# wifistation.net
KiCad netlist of a schematic drawn in EAGLE
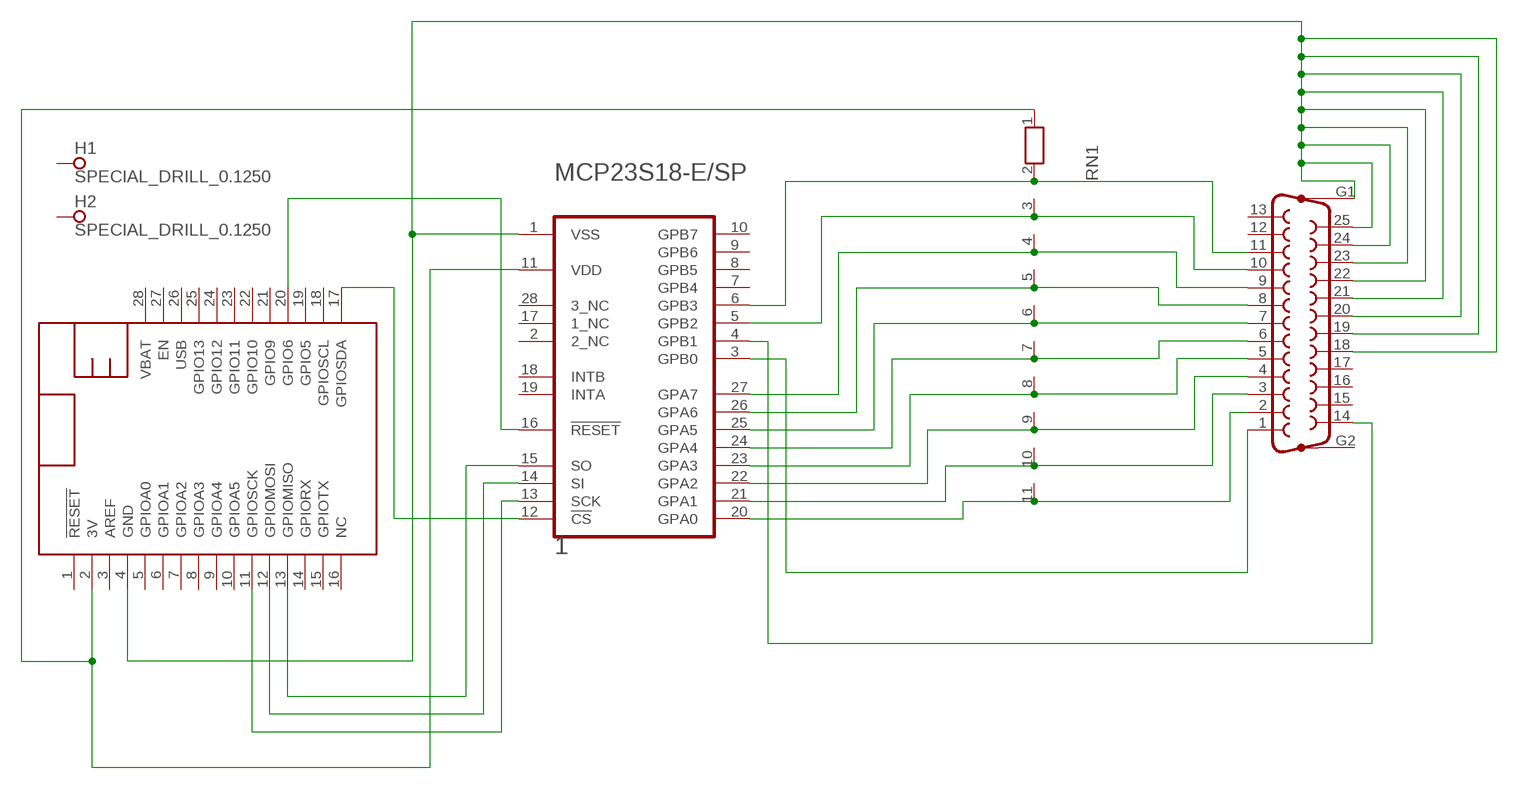
[diagram p0: schematic, sheet 1]

(export (version "E")
  (design (tool "Eeschema 10.0.6"))
  (components
    (comp (ref "1")
      (value "MICROCHIP_MCP23S18-E-SPMICROCHIP_MCP23S18-E-SP_0_0")
      (footprint "eagle-import:MICROCHIP_MCP23S18-E-SP_0")
      (fields (field (name "MF") "Microchip") (field (name "MPN") "MCP23S18-E/SP"))
      (libsource (lib "eagle-import") (part "MICROCHIP_MCP23S18-E-SPMICROCHIP_MCP23S18-E-SP_0_0"))
    )
    (comp (ref "DB25")
      (value "F25HP")
      (footprint "eagle-import:F25HP")
      (libsource (lib "eagle-import") (part "F25HP"))
    )
    (comp (ref "FEATHER")
      (value "FEATHERWING_NODIM_NOHOLES")
      (footprint "eagle-import:FEATHERWING_DIM")
      (libsource (lib "eagle-import") (part "FEATHERWING_NODIM_NOHOLES"))
    )
    (comp (ref "H1")
      (value "SPECIAL_DRILL_0.1250")
      (footprint "eagle-import:PAD_0.1250")
      (libsource (lib "eagle-import") (part "SPECIAL_DRILL_0.1250"))
    )
    (comp (ref "H2")
      (value "SPECIAL_DRILL_0.1250")
      (footprint "eagle-import:PAD_0.1250")
      (libsource (lib "eagle-import") (part "SPECIAL_DRILL_0.1250"))
    )
    (comp (ref "RN1")
      (value "RN10")
      (footprint "eagle-import:RN-11")
      (libsource (lib "eagle-import") (part "RN10"))
    )
  )
  (nets
    (net (code "1") (name "/USB") (class "Default")
      (node (ref "FEATHER") (pin "26") (pinfunction "USB_26") (pintype "power_in"))
    )
    (net (code "2") (name "/VBAT") (class "Default")
      (node (ref "FEATHER") (pin "28") (pinfunction "VBAT_28") (pintype "power_in"))
    )
    (net (code "3") (name "Net-(1-GPA0)") (class "Default")
      (node (ref "1") (pin "20") (pinfunction "GPA0_20") (pintype "bidirectional"))
      (node (ref "DB25") (pin "2") (pinfunction "2_2") (pintype "passive"))
      (node (ref "RN1") (pin "11") (pinfunction "11_11") (pintype "passive"))
    )
    (net (code "4") (name "Net-(1-GPA1)") (class "Default")
      (node (ref "1") (pin "21") (pinfunction "GPA1_21") (pintype "bidirectional"))
      (node (ref "DB25") (pin "3") (pinfunction "3_3") (pintype "passive"))
      (node (ref "RN1") (pin "10") (pinfunction "10_10") (pintype "passive"))
    )
    (net (code "5") (name "Net-(1-GPA2)") (class "Default")
      (node (ref "1") (pin "22") (pinfunction "GPA2_22") (pintype "bidirectional"))
      (node (ref "DB25") (pin "4") (pinfunction "4_4") (pintype "passive"))
      (node (ref "RN1") (pin "9") (pinfunction "9_9") (pintype "passive"))
    )
    (net (code "6") (name "Net-(1-GPA3)") (class "Default")
      (node (ref "1") (pin "23") (pinfunction "GPA3_23") (pintype "bidirectional"))
      (node (ref "DB25") (pin "5") (pinfunction "5_5") (pintype "passive"))
      (node (ref "RN1") (pin "8") (pinfunction "8_8") (pintype "passive"))
    )
    (net (code "7") (name "Net-(1-GPA4)") (class "Default")
      (node (ref "1") (pin "24") (pinfunction "GPA4_24") (pintype "bidirectional"))
      (node (ref "DB25") (pin "6") (pinfunction "6_6") (pintype "passive"))
      (node (ref "RN1") (pin "7") (pinfunction "7_7") (pintype "passive"))
    )
    (net (code "8") (name "Net-(1-GPA5)") (class "Default")
      (node (ref "1") (pin "25") (pinfunction "GPA5_25") (pintype "bidirectional"))
      (node (ref "DB25") (pin "7") (pinfunction "7_7") (pintype "passive"))
      (node (ref "RN1") (pin "6") (pinfunction "6_6") (pintype "passive"))
    )
    (net (code "9") (name "Net-(1-GPA6)") (class "Default")
      (node (ref "1") (pin "26") (pinfunction "GPA6_26") (pintype "bidirectional"))
      (node (ref "DB25") (pin "8") (pinfunction "8_8") (pintype "passive"))
      (node (ref "RN1") (pin "5") (pinfunction "5_5") (pintype "passive"))
    )
    (net (code "10") (name "Net-(1-GPA7)") (class "Default")
      (node (ref "1") (pin "27") (pinfunction "GPA7_27") (pintype "bidirectional"))
      (node (ref "DB25") (pin "9") (pinfunction "9_9") (pintype "passive"))
      (node (ref "RN1") (pin "4") (pinfunction "4_4") (pintype "passive"))
    )
    (net (code "11") (name "Net-(1-GPB0)") (class "Default")
      (node (ref "1") (pin "3") (pinfunction "GPB0_3") (pintype "bidirectional"))
      (node (ref "DB25") (pin "1") (pinfunction "1_1") (pintype "passive"))
    )
    (net (code "12") (name "Net-(1-GPB1)") (class "Default")
      (node (ref "1") (pin "4") (pinfunction "GPB1_4") (pintype "bidirectional"))
      (node (ref "DB25") (pin "14") (pinfunction "14_14") (pintype "passive"))
    )
    (net (code "13") (name "Net-(1-GPB2)") (class "Default")
      (node (ref "1") (pin "5") (pinfunction "GPB2_5") (pintype "bidirectional"))
      (node (ref "DB25") (pin "10") (pinfunction "10_10") (pintype "passive"))
      (node (ref "RN1") (pin "3") (pinfunction "3_3") (pintype "passive"))
    )
    (net (code "14") (name "Net-(1-GPB3)") (class "Default")
      (node (ref "1") (pin "6") (pinfunction "GPB3_6") (pintype "bidirectional"))
      (node (ref "DB25") (pin "11") (pinfunction "11_11") (pintype "passive"))
      (node (ref "RN1") (pin "2") (pinfunction "2_2") (pintype "passive"))
    )
    (net (code "15") (name "Net-(1-SCK)") (class "Default")
      (node (ref "1") (pin "13") (pinfunction "SCK_13") (pintype "input"))
      (node (ref "FEATHER") (pin "11") (pinfunction "GPIOSCK_11") (pintype "bidirectional"))
    )
    (net (code "16") (name "Net-(1-SI)") (class "Default")
      (node (ref "1") (pin "14") (pinfunction "SI_14") (pintype "input"))
      (node (ref "FEATHER") (pin "12") (pinfunction "GPIOMOSI_12") (pintype "bidirectional"))
    )
    (net (code "17") (name "Net-(1-SO)") (class "Default")
      (node (ref "1") (pin "15") (pinfunction "SO_15") (pintype "output"))
      (node (ref "FEATHER") (pin "13") (pinfunction "GPIOMISO_13") (pintype "bidirectional"))
    )
    (net (code "18") (name "Net-(1-VDD)") (class "Default")
      (node (ref "1") (pin "11") (pinfunction "VDD_11") (pintype "power_in"))
      (node (ref "FEATHER") (pin "2") (pinfunction "3V_2") (pintype "power_in"))
      (node (ref "RN1") (pin "1") (pinfunction "1_1") (pintype "passive"))
    )
    (net (code "19") (name "Net-(1-VSS)") (class "Default")
      (node (ref "1") (pin "1") (pinfunction "VSS_1") (pintype "power_in"))
      (node (ref "DB25") (pin "18") (pinfunction "18_18") (pintype "passive"))
      (node (ref "DB25") (pin "19") (pinfunction "19_19") (pintype "passive"))
      (node (ref "DB25") (pin "20") (pinfunction "20_20") (pintype "passive"))
      (node (ref "DB25") (pin "21") (pinfunction "21_21") (pintype "passive"))
      (node (ref "DB25") (pin "22") (pinfunction "22_22") (pintype "passive"))
      (node (ref "DB25") (pin "23") (pinfunction "23_23") (pintype "passive"))
      (node (ref "DB25") (pin "24") (pinfunction "24_24") (pintype "passive"))
      (node (ref "DB25") (pin "25") (pinfunction "25_25") (pintype "passive"))
      (node (ref "DB25") (pin "G1") (pinfunction "G1_G1") (pintype "passive"))
      (node (ref "FEATHER") (pin "4") (pinfunction "GND_4") (pintype "power_in"))
    )
    (net (code "20") (name "Net-(1-~{CS})") (class "Default")
      (node (ref "1") (pin "12") (pinfunction "~{CS}_12") (pintype "input"))
      (node (ref "FEATHER") (pin "17") (pinfunction "GPIOSDA_17") (pintype "bidirectional"))
    )
    (net (code "21") (name "Net-(1-~{RESET})") (class "Default")
      (node (ref "1") (pin "16") (pinfunction "~{RESET}_16") (pintype "input"))
      (node (ref "FEATHER") (pin "20") (pinfunction "GPIO6_20") (pintype "bidirectional"))
    )
    (net (code "22") (name "unconnected-(1-1_NC-Pad17)") (class "Default")
      (node (ref "1") (pin "17") (pinfunction "1_NC_17") (pintype "passive"))
    )
    (net (code "23") (name "unconnected-(1-2_NC-Pad2)") (class "Default")
      (node (ref "1") (pin "2") (pinfunction "2_NC_2") (pintype "passive"))
    )
    (net (code "24") (name "unconnected-(1-3_NC-Pad28)") (class "Default")
      (node (ref "1") (pin "28") (pinfunction "3_NC_28") (pintype "passive"))
    )
    (net (code "25") (name "unconnected-(1-GPB4-Pad7)") (class "Default")
      (node (ref "1") (pin "7") (pinfunction "GPB4_7") (pintype "bidirectional"))
    )
    (net (code "26") (name "unconnected-(1-GPB5-Pad8)") (class "Default")
      (node (ref "1") (pin "8") (pinfunction "GPB5_8") (pintype "bidirectional"))
    )
    (net (code "27") (name "unconnected-(1-GPB6-Pad9)") (class "Default")
      (node (ref "1") (pin "9") (pinfunction "GPB6_9") (pintype "bidirectional"))
    )
    (net (code "28") (name "unconnected-(1-GPB7-Pad10)") (class "Default")
      (node (ref "1") (pin "10") (pinfunction "GPB7_10") (pintype "bidirectional"))
    )
    (net (code "29") (name "unconnected-(1-INTA-Pad19)") (class "Default")
      (node (ref "1") (pin "19") (pinfunction "INTA_19") (pintype "open_collector"))
    )
    (net (code "30") (name "unconnected-(1-INTB-Pad18)") (class "Default")
      (node (ref "1") (pin "18") (pinfunction "INTB_18") (pintype "open_collector"))
    )
    (net (code "31") (name "unconnected-(DB25-Pad12)") (class "Default")
      (node (ref "DB25") (pin "12") (pinfunction "12_12") (pintype "passive"))
    )
    (net (code "32") (name "unconnected-(DB25-Pad13)") (class "Default")
      (node (ref "DB25") (pin "13") (pinfunction "13_13") (pintype "passive"))
    )
    (net (code "33") (name "unconnected-(DB25-Pad15)") (class "Default")
      (node (ref "DB25") (pin "15") (pinfunction "15_15") (pintype "passive"))
    )
    (net (code "34") (name "unconnected-(DB25-Pad16)") (class "Default")
      (node (ref "DB25") (pin "16") (pinfunction "16_16") (pintype "passive"))
    )
    (net (code "35") (name "unconnected-(DB25-Pad17)") (class "Default")
      (node (ref "DB25") (pin "17") (pinfunction "17_17") (pintype "passive"))
    )
    (net (code "36") (name "unconnected-(DB25-PadG2)") (class "Default")
      (node (ref "DB25") (pin "G2") (pinfunction "G2_G2") (pintype "passive"))
    )
    (net (code "37") (name "unconnected-(FEATHER-AREF-Pad3)") (class "Default")
      (node (ref "FEATHER") (pin "3") (pinfunction "AREF_3") (pintype "passive"))
    )
    (net (code "38") (name "unconnected-(FEATHER-EN-Pad27)") (class "Default")
      (node (ref "FEATHER") (pin "27") (pinfunction "EN_27") (pintype "passive"))
    )
    (net (code "39") (name "unconnected-(FEATHER-GPIO5-Pad19)") (class "Default")
      (node (ref "FEATHER") (pin "19") (pinfunction "GPIO5_19") (pintype "bidirectional"))
    )
    (net (code "40") (name "unconnected-(FEATHER-GPIO9-Pad21)") (class "Default")
      (node (ref "FEATHER") (pin "21") (pinfunction "GPIO9_21") (pintype "bidirectional"))
    )
    (net (code "41") (name "unconnected-(FEATHER-GPIO10-Pad22)") (class "Default")
      (node (ref "FEATHER") (pin "22") (pinfunction "GPIO10_22") (pintype "bidirectional"))
    )
    (net (code "42") (name "unconnected-(FEATHER-GPIO11-Pad23)") (class "Default")
      (node (ref "FEATHER") (pin "23") (pinfunction "GPIO11_23") (pintype "bidirectional"))
    )
    (net (code "43") (name "unconnected-(FEATHER-GPIO12-Pad24)") (class "Default")
      (node (ref "FEATHER") (pin "24") (pinfunction "GPIO12_24") (pintype "bidirectional"))
    )
    (net (code "44") (name "unconnected-(FEATHER-GPIO13-Pad25)") (class "Default")
      (node (ref "FEATHER") (pin "25") (pinfunction "GPIO13_25") (pintype "bidirectional"))
    )
    (net (code "45") (name "unconnected-(FEATHER-GPIOA0-Pad5)") (class "Default")
      (node (ref "FEATHER") (pin "5") (pinfunction "GPIOA0_5") (pintype "bidirectional"))
    )
    (net (code "46") (name "unconnected-(FEATHER-GPIOA1-Pad6)") (class "Default")
      (node (ref "FEATHER") (pin "6") (pinfunction "GPIOA1_6") (pintype "bidirectional"))
    )
    (net (code "47") (name "unconnected-(FEATHER-GPIOA2-Pad7)") (class "Default")
      (node (ref "FEATHER") (pin "7") (pinfunction "GPIOA2_7") (pintype "bidirectional"))
    )
    (net (code "48") (name "unconnected-(FEATHER-GPIOA3-Pad8)") (class "Default")
      (node (ref "FEATHER") (pin "8") (pinfunction "GPIOA3_8") (pintype "bidirectional"))
    )
    (net (code "49") (name "unconnected-(FEATHER-GPIOA4-Pad9)") (class "Default")
      (node (ref "FEATHER") (pin "9") (pinfunction "GPIOA4_9") (pintype "bidirectional"))
    )
    (net (code "50") (name "unconnected-(FEATHER-GPIOA5-Pad10)") (class "Default")
      (node (ref "FEATHER") (pin "10") (pinfunction "GPIOA5_10") (pintype "bidirectional"))
    )
    (net (code "51") (name "unconnected-(FEATHER-GPIORX-Pad14)") (class "Default")
      (node (ref "FEATHER") (pin "14") (pinfunction "GPIORX_14") (pintype "bidirectional"))
    )
    (net (code "52") (name "unconnected-(FEATHER-GPIOSCL-Pad18)") (class "Default")
      (node (ref "FEATHER") (pin "18") (pinfunction "GPIOSCL_18") (pintype "bidirectional"))
    )
    (net (code "53") (name "unconnected-(FEATHER-GPIOTX-Pad15)") (class "Default")
      (node (ref "FEATHER") (pin "15") (pinfunction "GPIOTX_15") (pintype "bidirectional"))
    )
    (net (code "54") (name "unconnected-(FEATHER-NC-Pad16)") (class "Default")
      (node (ref "FEATHER") (pin "16") (pinfunction "NC_16") (pintype "passive"))
    )
    (net (code "55") (name "unconnected-(FEATHER-~{RESET}-Pad1)") (class "Default")
      (node (ref "FEATHER") (pin "1") (pinfunction "~{RESET}_1") (pintype "input"))
    )
    (net (code "56") (name "unconnected-(H1-Pad1)") (class "Default")
      (node (ref "H1") (pin "1") (pinfunction "1_1") (pintype "passive"))
    )
    (net (code "57") (name "unconnected-(H2-Pad1)") (class "Default")
      (node (ref "H2") (pin "1") (pinfunction "1_1") (pintype "passive"))
    )
  )
)
